# Fram_schematic.net
KiCad netlist of a schematic drawn in EAGLE
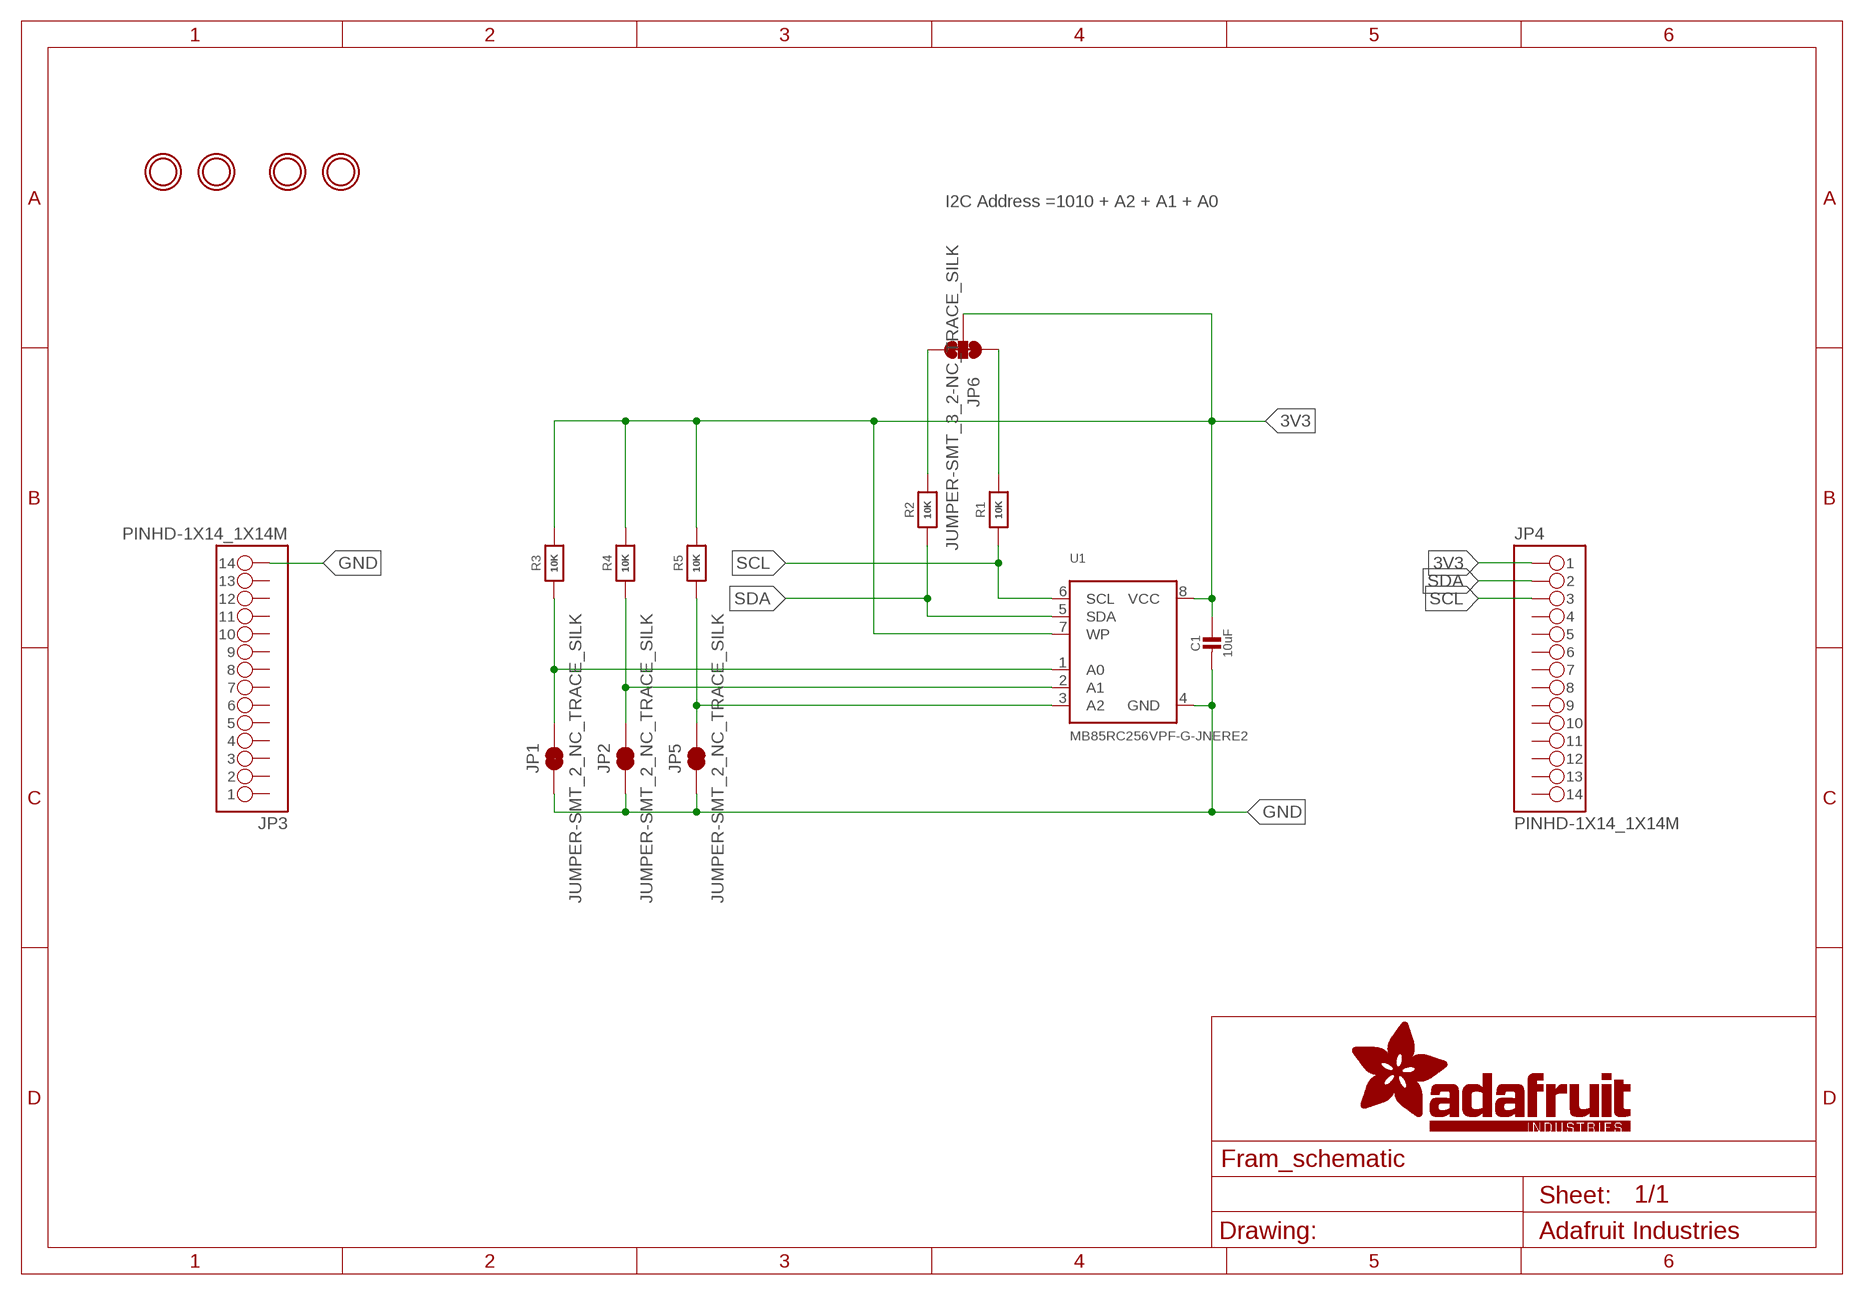
[diagram p0: schematic, sheet 1]

(export (version "E")
  (design (tool "Eeschema 10.0.6"))
  (components
    (comp (ref "C1")
      (value "10uF")
      (footprint "eagle-import:_0805MP")
      (libsource (lib "eagle-import") (part "CAP_CERAMIC_0805MP"))
    )
    (comp (ref "JP1")
      (value "JUMPER-SMT_2_NC_TRACE_SILK")
      (footprint "eagle-import:SMT-JUMPER_2_NC_TRACE_SILK")
      (libsource (lib "eagle-import") (part "JUMPER-SMT_2_NC_TRACE_SILK"))
    )
    (comp (ref "JP2")
      (value "JUMPER-SMT_2_NC_TRACE_SILK")
      (footprint "eagle-import:SMT-JUMPER_2_NC_TRACE_SILK")
      (libsource (lib "eagle-import") (part "JUMPER-SMT_2_NC_TRACE_SILK"))
    )
    (comp (ref "JP3")
      (value "PINHD-1X14_1X14M")
      (footprint "eagle-import:1X14")
      (libsource (lib "eagle-import") (part "PINHD-1X14_1X14M"))
    )
    (comp (ref "JP4")
      (value "PINHD-1X14_1X14M")
      (footprint "eagle-import:1X14")
      (libsource (lib "eagle-import") (part "PINHD-1X14_1X14M"))
    )
    (comp (ref "JP5")
      (value "JUMPER-SMT_2_NC_TRACE_SILK")
      (footprint "eagle-import:SMT-JUMPER_2_NC_TRACE_SILK")
      (libsource (lib "eagle-import") (part "JUMPER-SMT_2_NC_TRACE_SILK"))
    )
    (comp (ref "JP6")
      (value "JUMPER-SMT_3_2-NC_TRACE_SILK")
      (footprint "eagle-import:SMT-JUMPER_3_2-NC_TRACE_SILK")
      (libsource (lib "eagle-import") (part "JUMPER-SMT_3_2-NC_TRACE_SILK"))
    )
    (comp (ref "R1")
      (value "10K")
      (footprint "eagle-import:_0805MP")
      (libsource (lib "eagle-import") (part "RESISTOR_0805MP"))
    )
    (comp (ref "R2")
      (value "10K")
      (footprint "eagle-import:_0805MP")
      (libsource (lib "eagle-import") (part "RESISTOR_0805MP"))
    )
    (comp (ref "R3")
      (value "10K")
      (footprint "eagle-import:_0805MP")
      (libsource (lib "eagle-import") (part "RESISTOR_0805MP"))
    )
    (comp (ref "R4")
      (value "10K")
      (footprint "eagle-import:_0805MP")
      (libsource (lib "eagle-import") (part "RESISTOR_0805MP"))
    )
    (comp (ref "R5")
      (value "10K")
      (footprint "eagle-import:_0805MP")
      (libsource (lib "eagle-import") (part "RESISTOR_0805MP"))
    )
    (comp (ref "U$2")
      (value "MOUNTINGHOLE2.5")
      (footprint "eagle-import:MOUNTINGHOLE_2.5_PLATED")
      (libsource (lib "eagle-import") (part "MOUNTINGHOLE2.5"))
    )
    (comp (ref "U$3")
      (value "MOUNTINGHOLE2.5")
      (footprint "eagle-import:MOUNTINGHOLE_2.5_PLATED")
      (libsource (lib "eagle-import") (part "MOUNTINGHOLE2.5"))
    )
    (comp (ref "U$5")
      (value "MOUNTINGHOLE2.5")
      (footprint "eagle-import:MOUNTINGHOLE_2.5_PLATED")
      (libsource (lib "eagle-import") (part "MOUNTINGHOLE2.5"))
    )
    (comp (ref "U$6")
      (value "MOUNTINGHOLE2.5")
      (footprint "eagle-import:MOUNTINGHOLE_2.5_PLATED")
      (libsource (lib "eagle-import") (part "MOUNTINGHOLE2.5"))
    )
    (comp (ref "U1")
      (value "MB85RC256VPF-G-JNERE2")
      (footprint "eagle-import:SOIC8_208MIL")
      (libsource (lib "eagle-import") (part "FRAM_SOIC8_I2C"))
    )
  )
  (nets
    (net (code "1") (name "3V3") (class "Default")
      (node (ref "C1") (pin "1") (pinfunction "1_1") (pintype "passive"))
      (node (ref "JP4") (pin "1") (pinfunction "1_1") (pintype "bidirectional"))
      (node (ref "JP6") (pin "2") (pinfunction "2_2") (pintype "passive"))
      (node (ref "R3") (pin "2") (pinfunction "2_2") (pintype "passive"))
      (node (ref "R4") (pin "2") (pinfunction "2_2") (pintype "passive"))
      (node (ref "R5") (pin "2") (pinfunction "2_2") (pintype "passive"))
      (node (ref "U1") (pin "7") (pinfunction "WP_7") (pintype "input"))
      (node (ref "U1") (pin "8") (pinfunction "VCC_8") (pintype "power_in"))
    )
    (net (code "2") (name "GND") (class "Default")
      (node (ref "C1") (pin "2") (pinfunction "2_2") (pintype "passive"))
      (node (ref "JP1") (pin "1") (pinfunction "1_1") (pintype "passive"))
      (node (ref "JP2") (pin "1") (pinfunction "1_1") (pintype "passive"))
      (node (ref "JP3") (pin "14") (pinfunction "14_14") (pintype "bidirectional"))
      (node (ref "JP5") (pin "1") (pinfunction "1_1") (pintype "passive"))
      (node (ref "U1") (pin "4") (pinfunction "GND_4") (pintype "power_in"))
    )
    (net (code "3") (name "Net-(U1-A0)") (class "Default")
      (node (ref "JP1") (pin "2") (pinfunction "2_2") (pintype "passive"))
      (node (ref "R3") (pin "1") (pinfunction "1_1") (pintype "passive"))
      (node (ref "U1") (pin "1") (pinfunction "A0_1") (pintype "input"))
    )
    (net (code "4") (name "Net-(U1-A1)") (class "Default")
      (node (ref "JP2") (pin "2") (pinfunction "2_2") (pintype "passive"))
      (node (ref "R4") (pin "1") (pinfunction "1_1") (pintype "passive"))
      (node (ref "U1") (pin "2") (pinfunction "A1_2") (pintype "input"))
    )
    (net (code "5") (name "Net-(U1-A2)") (class "Default")
      (node (ref "JP5") (pin "2") (pinfunction "2_2") (pintype "passive"))
      (node (ref "R5") (pin "1") (pinfunction "1_1") (pintype "passive"))
      (node (ref "U1") (pin "3") (pinfunction "A2_3") (pintype "input"))
    )
    (net (code "6") (name "SCL") (class "Default")
      (node (ref "JP4") (pin "3") (pinfunction "3_3") (pintype "bidirectional"))
      (node (ref "JP6") (pin "1") (pinfunction "1_1") (pintype "passive"))
      (node (ref "R1") (pin "1") (pinfunction "1_1") (pintype "passive"))
      (node (ref "R1") (pin "2") (pinfunction "2_2") (pintype "passive"))
      (node (ref "U1") (pin "6") (pinfunction "SCL_6") (pintype "input"))
    )
    (net (code "7") (name "SDA") (class "Default")
      (node (ref "JP4") (pin "2") (pinfunction "2_2") (pintype "bidirectional"))
      (node (ref "JP6") (pin "3") (pinfunction "3_3") (pintype "passive"))
      (node (ref "R2") (pin "1") (pinfunction "1_1") (pintype "passive"))
      (node (ref "R2") (pin "2") (pinfunction "2_2") (pintype "passive"))
      (node (ref "U1") (pin "5") (pinfunction "SDA_5") (pintype "bidirectional"))
    )
    (net (code "8") (name "unconnected-(JP3-Pad1)") (class "Default")
      (node (ref "JP3") (pin "1") (pinfunction "1_1") (pintype "bidirectional"))
    )
    (net (code "9") (name "unconnected-(JP3-Pad2)") (class "Default")
      (node (ref "JP3") (pin "2") (pinfunction "2_2") (pintype "bidirectional"))
    )
    (net (code "10") (name "unconnected-(JP3-Pad3)") (class "Default")
      (node (ref "JP3") (pin "3") (pinfunction "3_3") (pintype "bidirectional"))
    )
    (net (code "11") (name "unconnected-(JP3-Pad4)") (class "Default")
      (node (ref "JP3") (pin "4") (pinfunction "4_4") (pintype "bidirectional"))
    )
    (net (code "12") (name "unconnected-(JP3-Pad5)") (class "Default")
      (node (ref "JP3") (pin "5") (pinfunction "5_5") (pintype "bidirectional"))
    )
    (net (code "13") (name "unconnected-(JP3-Pad6)") (class "Default")
      (node (ref "JP3") (pin "6") (pinfunction "6_6") (pintype "bidirectional"))
    )
    (net (code "14") (name "unconnected-(JP3-Pad7)") (class "Default")
      (node (ref "JP3") (pin "7") (pinfunction "7_7") (pintype "bidirectional"))
    )
    (net (code "15") (name "unconnected-(JP3-Pad8)") (class "Default")
      (node (ref "JP3") (pin "8") (pinfunction "8_8") (pintype "bidirectional"))
    )
    (net (code "16") (name "unconnected-(JP3-Pad9)") (class "Default")
      (node (ref "JP3") (pin "9") (pinfunction "9_9") (pintype "bidirectional"))
    )
    (net (code "17") (name "unconnected-(JP3-Pad10)") (class "Default")
      (node (ref "JP3") (pin "10") (pinfunction "10_10") (pintype "bidirectional"))
    )
    (net (code "18") (name "unconnected-(JP3-Pad11)") (class "Default")
      (node (ref "JP3") (pin "11") (pinfunction "11_11") (pintype "bidirectional"))
    )
    (net (code "19") (name "unconnected-(JP3-Pad12)") (class "Default")
      (node (ref "JP3") (pin "12") (pinfunction "12_12") (pintype "bidirectional"))
    )
    (net (code "20") (name "unconnected-(JP3-Pad13)") (class "Default")
      (node (ref "JP3") (pin "13") (pinfunction "13_13") (pintype "bidirectional"))
    )
    (net (code "21") (name "unconnected-(JP4-Pad4)") (class "Default")
      (node (ref "JP4") (pin "4") (pinfunction "4_4") (pintype "bidirectional"))
    )
    (net (code "22") (name "unconnected-(JP4-Pad5)") (class "Default")
      (node (ref "JP4") (pin "5") (pinfunction "5_5") (pintype "bidirectional"))
    )
    (net (code "23") (name "unconnected-(JP4-Pad6)") (class "Default")
      (node (ref "JP4") (pin "6") (pinfunction "6_6") (pintype "bidirectional"))
    )
    (net (code "24") (name "unconnected-(JP4-Pad7)") (class "Default")
      (node (ref "JP4") (pin "7") (pinfunction "7_7") (pintype "bidirectional"))
    )
    (net (code "25") (name "unconnected-(JP4-Pad8)") (class "Default")
      (node (ref "JP4") (pin "8") (pinfunction "8_8") (pintype "bidirectional"))
    )
    (net (code "26") (name "unconnected-(JP4-Pad9)") (class "Default")
      (node (ref "JP4") (pin "9") (pinfunction "9_9") (pintype "bidirectional"))
    )
    (net (code "27") (name "unconnected-(JP4-Pad10)") (class "Default")
      (node (ref "JP4") (pin "10") (pinfunction "10_10") (pintype "bidirectional"))
    )
    (net (code "28") (name "unconnected-(JP4-Pad11)") (class "Default")
      (node (ref "JP4") (pin "11") (pinfunction "11_11") (pintype "bidirectional"))
    )
    (net (code "29") (name "unconnected-(JP4-Pad12)") (class "Default")
      (node (ref "JP4") (pin "12") (pinfunction "12_12") (pintype "bidirectional"))
    )
    (net (code "30") (name "unconnected-(JP4-Pad13)") (class "Default")
      (node (ref "JP4") (pin "13") (pinfunction "13_13") (pintype "bidirectional"))
    )
    (net (code "31") (name "unconnected-(JP4-Pad14)") (class "Default")
      (node (ref "JP4") (pin "14") (pinfunction "14_14") (pintype "bidirectional"))
    )
  )
)
